# I2C_MUX.net
KiCad netlist of a schematic drawn in Altium Designer
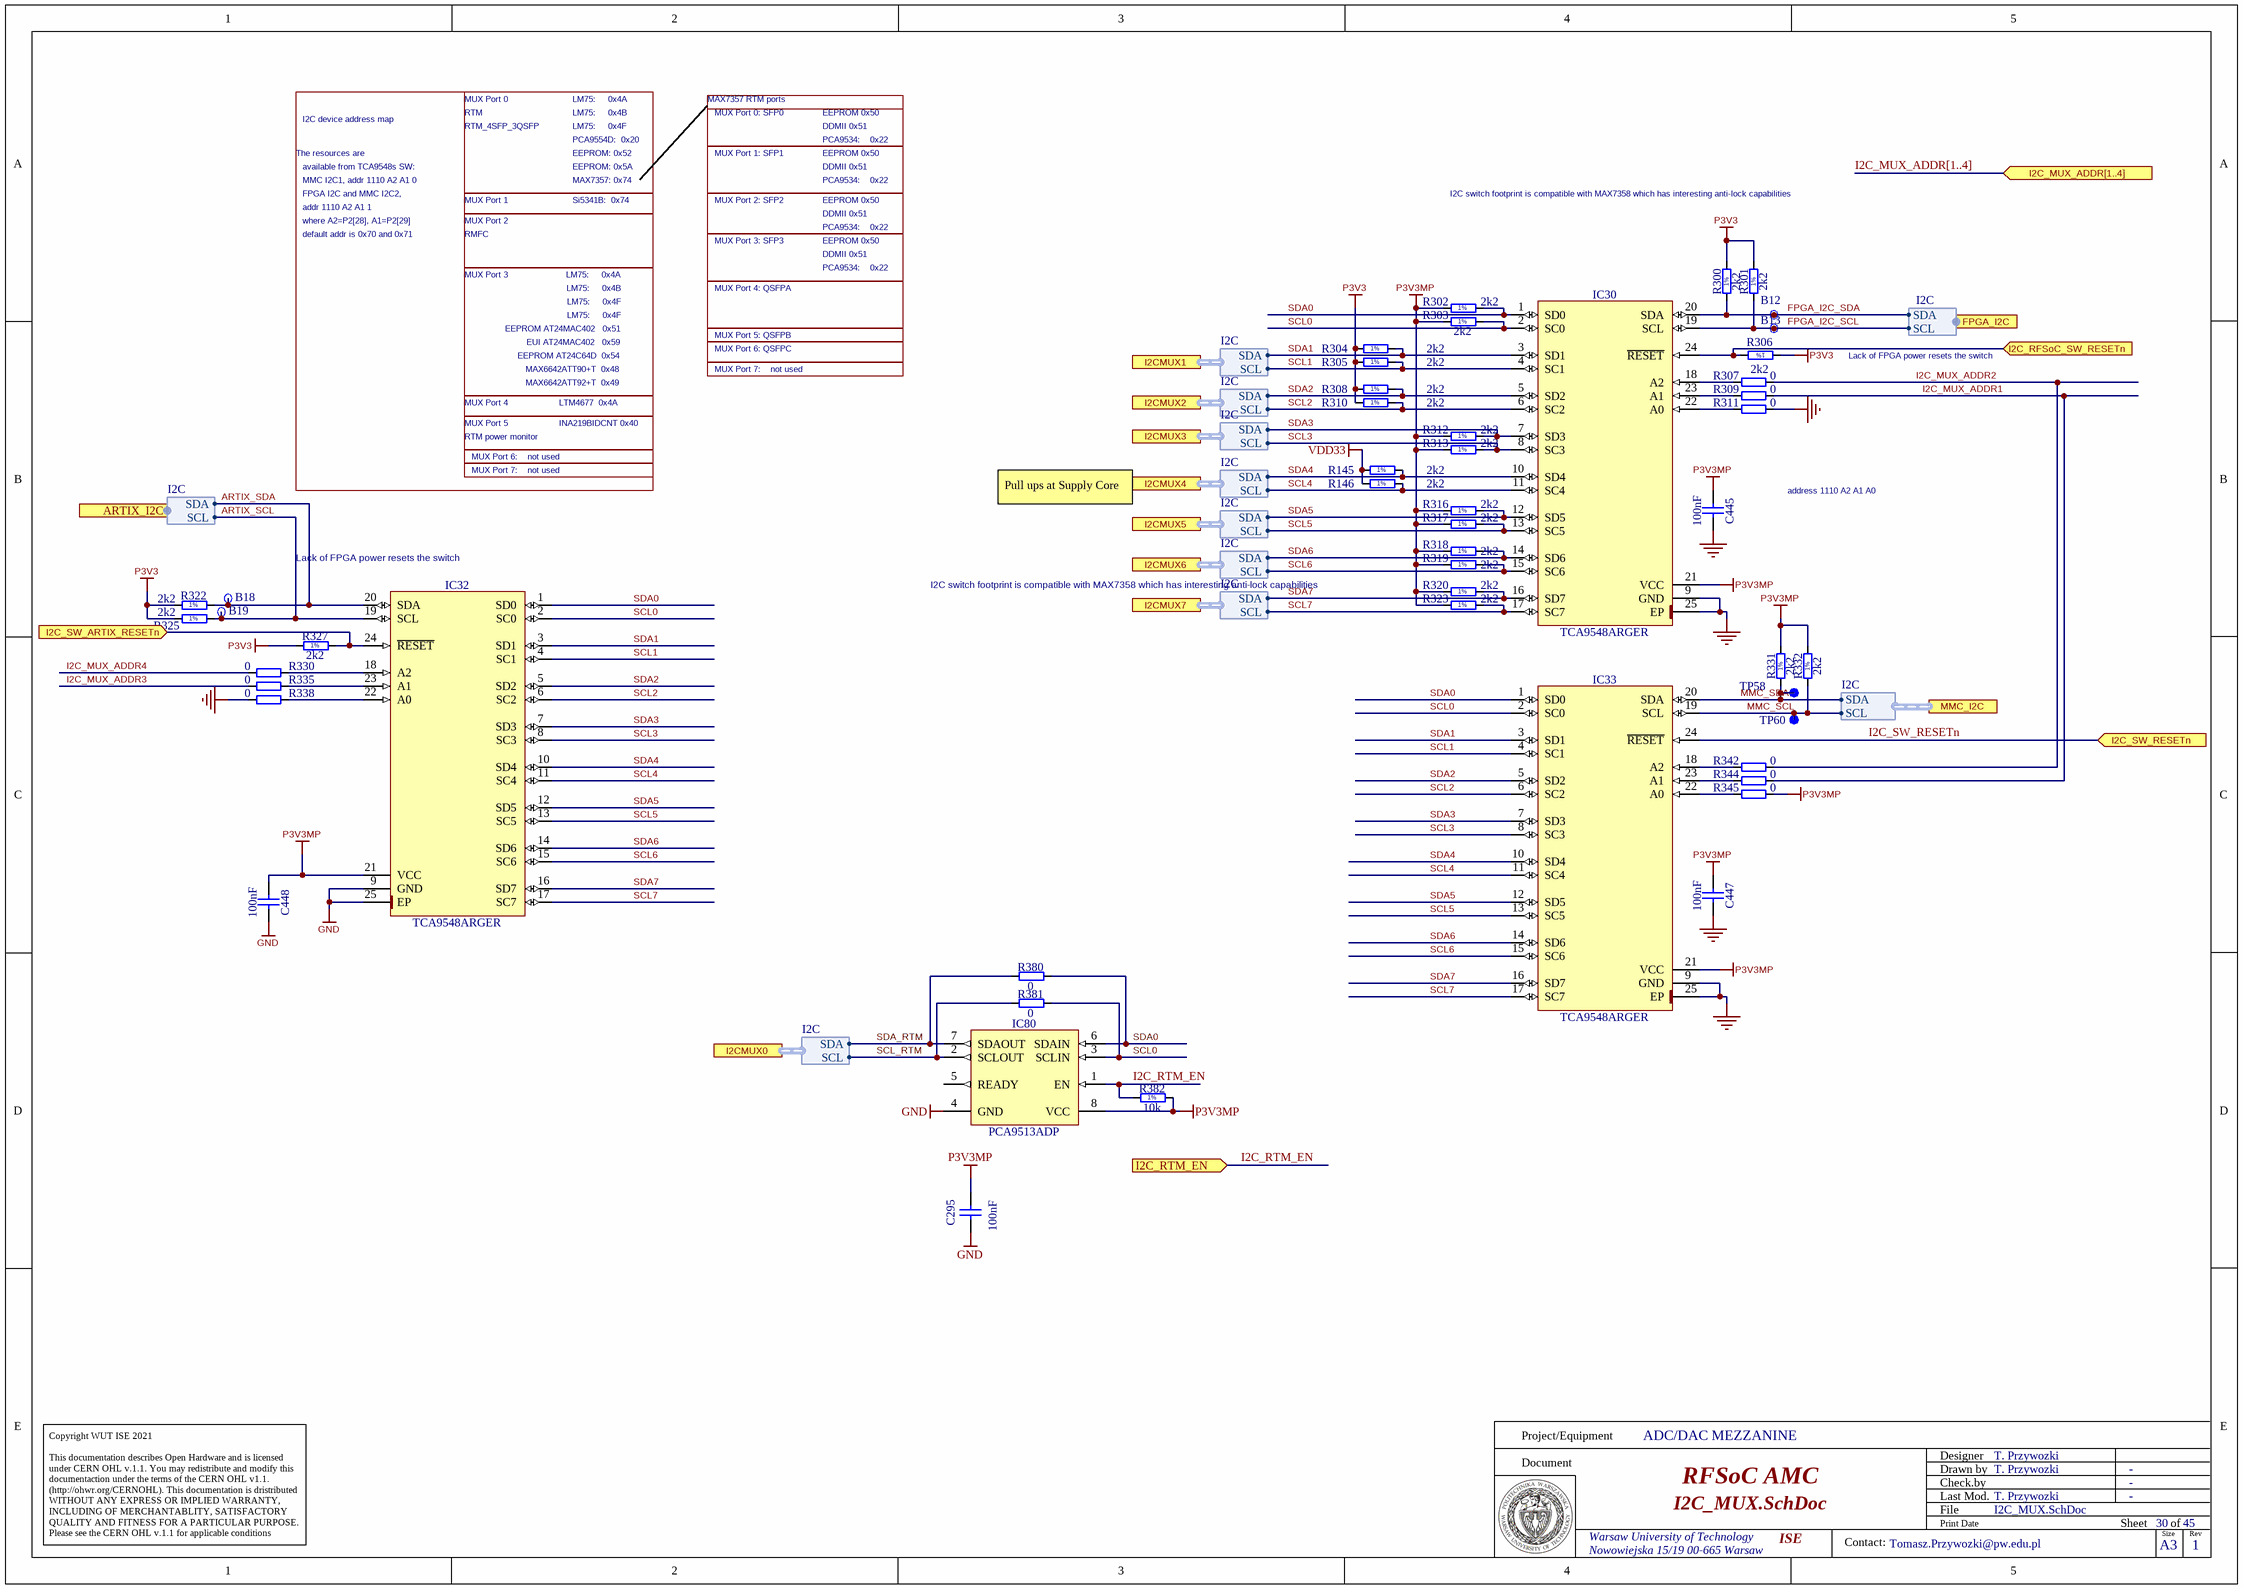
[diagram p0: I2C_MUX.SchDoc]

(export (version "E")
  (design (tool "Eeschema 10.0.6"))
  (components
    (comp (ref "B12")
      (value "SMD_PAD_D1MM")
      (footprint "C100")
      (libsource (lib "altium-import") (part "root_0__*"))
    )
    (comp (ref "B13")
      (value "SMD_PAD_D1MM")
      (footprint "C100")
      (libsource (lib "altium-import") (part "root_0__*"))
    )
    (comp (ref "B18")
      (value "SMD_PAD_D1MM")
      (footprint "C100")
      (libsource (lib "altium-import") (part "root_0__*"))
    )
    (comp (ref "B19")
      (value "SMD_PAD_D1MM")
      (footprint "C100")
      (libsource (lib "altium-import") (part "root_0__*"))
    )
    (comp (ref "C295")
      (value "100nF")
      (footprint "CAPC0603X33N")
      (description "Non-polarised capacitor")
      (fields
        (field (name "MANUFACTURER PART NUMBER") "CC0201_100NF_6.3V_10%_X5R")
        (field (name "MANUFACTURER") "GENERIC")
        (field (name "AUTHOR") "CERN DEM JLC")
      )
      (libsource (lib "Capacitors") (part "Capacitor - non polarized"))
    )
    (comp (ref "C445")
      (value "100nF")
      (footprint "CAPC0603X33N")
      (description "Non-polarised capacitor")
      (fields
        (field (name "MANUFACTURER PART NUMBER") "CC0201_100NF_6.3V_10%_X5R")
        (field (name "MANUFACTURER") "GENERIC")
        (field (name "AUTHOR") "CERN DEM JLC")
      )
      (libsource (lib "Capacitors") (part "Capacitor - non polarized"))
    )
    (comp (ref "C447")
      (value "100nF")
      (footprint "CAPC0603X33N")
      (description "Non-polarised capacitor")
      (fields
        (field (name "MANUFACTURER PART NUMBER") "CC0201_100NF_6.3V_10%_X5R")
        (field (name "MANUFACTURER") "GENERIC")
        (field (name "AUTHOR") "CERN DEM JLC")
      )
      (libsource (lib "Capacitors") (part "Capacitor - non polarized"))
    )
    (comp (ref "C448")
      (value "100nF")
      (footprint "CAPC0603X33N")
      (description "Non-polarised capacitor")
      (fields
        (field (name "MANUFACTURER PART NUMBER") "CC0201_100NF_6.3V_10%_X5R")
        (field (name "MANUFACTURER") "GENERIC")
        (field (name "AUTHOR") "CERN DEM JLC")
      )
      (libsource (lib "Capacitors") (part "Capacitor - non polarized"))
    )
    (comp (ref "IC30")
      (value "TCA9548ARGER")
      (footprint "QFN50P400X400X100-25N-S220")
      (description "Low Voltage 8-Channel I2C Switch With Reset")
      (fields (field (name "MANUFACTURER") "TEXAS INSTRUMENTS") (field (name "AUTHOR") "CERN DEM JLC"))
      (libsource (lib "") (part "TCA9548ARGER_1"))
    )
    (comp (ref "IC32")
      (value "TCA9548ARGER")
      (footprint "QFN50P400X400X100-25N-S220")
      (description "Low Voltage 8-Channel I2C Switch With Reset")
      (fields (field (name "MANUFACTURER") "TEXAS INSTRUMENTS") (field (name "AUTHOR") "CERN DEM JLC"))
      (libsource (lib "ICs And Semiconductors") (part "TCA9548ARGER"))
    )
    (comp (ref "IC33")
      (value "TCA9548ARGER")
      (footprint "QFN50P400X400X100-25N-S220")
      (description "Low Voltage 8-Channel I2C Switch With Reset")
      (fields (field (name "MANUFACTURER") "TEXAS INSTRUMENTS") (field (name "AUTHOR") "CERN DEM JLC"))
      (libsource (lib "") (part "TCA9548ARGER_1"))
    )
    (comp (ref "IC80")
      (value "PCA9513ADP")
      (footprint "SOP65P490X110-8N")
      (description "Hot Swappable I2C-Bus and SMBus Bus Buffer")
      (fields (field (name "MANUFACTURER") "NXP SEMICONDUCTORS") (field (name "AUTHOR") "CERN DEM MR"))
      (libsource (lib "ICs And Semiconductors") (part "PCA9513A"))
    )
    (comp (ref "R145")
      (value "2k2")
      (footprint "RESC1005X40N")
      (description "Resistor - 1%")
      (fields
        (field (name "MANUFACTURER PART NUMBER") "R0402_2K2_1%_0.0625W_100PPM")
        (field (name "MANUFACTURER") "GENERIC")
        (field (name "AUTHOR") "CERN DEM JLC")
      )
      (libsource (lib "Resistors") (part "Resistor - 1%"))
    )
    (comp (ref "R146")
      (value "2k2")
      (footprint "RESC1005X40N")
      (description "Resistor - 1%")
      (fields
        (field (name "MANUFACTURER PART NUMBER") "R0402_2K2_1%_0.0625W_100PPM")
        (field (name "MANUFACTURER") "GENERIC")
        (field (name "AUTHOR") "CERN DEM JLC")
      )
      (libsource (lib "Resistors") (part "Resistor - 1%"))
    )
    (comp (ref "R300")
      (value "2k2")
      (footprint "RESC1005X40N")
      (description "Resistor - 1%")
      (fields
        (field (name "MANUFACTURER PART NUMBER") "R0402_2K2_1%_0.0625W_100PPM")
        (field (name "MANUFACTURER") "GENERIC")
        (field (name "AUTHOR") "CERN DEM JLC")
      )
      (libsource (lib "Resistors") (part "Resistor - 1%"))
    )
    (comp (ref "R301")
      (value "2k2")
      (footprint "RESC1005X40N")
      (description "Resistor - 1%")
      (fields
        (field (name "MANUFACTURER PART NUMBER") "R0402_2K2_1%_0.0625W_100PPM")
        (field (name "MANUFACTURER") "GENERIC")
        (field (name "AUTHOR") "CERN DEM JLC")
      )
      (libsource (lib "Resistors") (part "Resistor - 1%"))
    )
    (comp (ref "R302")
      (value "2k2")
      (footprint "RESC1005X40N")
      (description "Resistor - 1%")
      (fields
        (field (name "MANUFACTURER PART NUMBER") "R0402_2K2_1%_0.0625W_100PPM")
        (field (name "MANUFACTURER") "GENERIC")
        (field (name "AUTHOR") "CERN DEM JLC")
      )
      (libsource (lib "Resistors") (part "Resistor - 1%"))
    )
    (comp (ref "R303")
      (value "2k2")
      (footprint "RESC1005X40N")
      (description "Resistor - 1%")
      (fields
        (field (name "MANUFACTURER PART NUMBER") "R0402_2K2_1%_0.0625W_100PPM")
        (field (name "MANUFACTURER") "GENERIC")
        (field (name "AUTHOR") "CERN DEM JLC")
      )
      (libsource (lib "Resistors") (part "Resistor - 1%"))
    )
    (comp (ref "R304")
      (value "2k2")
      (footprint "RESC1005X40N")
      (description "Resistor - 1%")
      (fields
        (field (name "MANUFACTURER PART NUMBER") "R0402_2K2_1%_0.0625W_100PPM")
        (field (name "MANUFACTURER") "GENERIC")
        (field (name "AUTHOR") "CERN DEM JLC")
      )
      (libsource (lib "Resistors") (part "Resistor - 1%"))
    )
    (comp (ref "R305")
      (value "2k2")
      (footprint "RESC1005X40N")
      (description "Resistor - 1%")
      (fields
        (field (name "MANUFACTURER PART NUMBER") "R0402_2K2_1%_0.0625W_100PPM")
        (field (name "MANUFACTURER") "GENERIC")
        (field (name "AUTHOR") "CERN DEM JLC")
      )
      (libsource (lib "Resistors") (part "Resistor - 1%"))
    )
    (comp (ref "R306")
      (value "2k2")
      (footprint "RESC1005X40N")
      (description "Resistor - 1%")
      (fields
        (field (name "MANUFACTURER PART NUMBER") "R0402_2K2_1%_0.0625W_100PPM")
        (field (name "MANUFACTURER") "GENERIC")
        (field (name "AUTHOR") "CERN DEM JLC")
      )
      (libsource (lib "Resistors") (part "Resistor - 1%"))
    )
    (comp (ref "R307")
      (value "0")
      (footprint "RESC1005X40N")
      (description "Resistor")
      (fields
        (field (name "MANUFACTURER PART NUMBER") "R0402_0R_JUMPER")
        (field (name "MANUFACTURER") "GENERIC")
        (field (name "AUTHOR") "CERN DEM JLC")
      )
      (libsource (lib "Resistors") (part "Resistor"))
    )
    (comp (ref "R308")
      (value "2k2")
      (footprint "RESC1005X40N")
      (description "Resistor - 1%")
      (fields
        (field (name "MANUFACTURER PART NUMBER") "R0402_2K2_1%_0.0625W_100PPM")
        (field (name "MANUFACTURER") "GENERIC")
        (field (name "AUTHOR") "CERN DEM JLC")
      )
      (libsource (lib "Resistors") (part "Resistor - 1%"))
    )
    (comp (ref "R309")
      (value "0")
      (footprint "RESC1005X40N")
      (description "Resistor")
      (fields
        (field (name "MANUFACTURER PART NUMBER") "R0402_0R_JUMPER")
        (field (name "MANUFACTURER") "GENERIC")
        (field (name "AUTHOR") "CERN DEM JLC")
      )
      (libsource (lib "Resistors") (part "Resistor"))
    )
    (comp (ref "R310")
      (value "2k2")
      (footprint "RESC1005X40N")
      (description "Resistor - 1%")
      (fields
        (field (name "MANUFACTURER PART NUMBER") "R0402_2K2_1%_0.0625W_100PPM")
        (field (name "MANUFACTURER") "GENERIC")
        (field (name "AUTHOR") "CERN DEM JLC")
      )
      (libsource (lib "Resistors") (part "Resistor - 1%"))
    )
    (comp (ref "R311")
      (value "0")
      (footprint "RESC1005X40N")
      (description "Resistor")
      (fields
        (field (name "MANUFACTURER PART NUMBER") "R0402_0R_JUMPER")
        (field (name "MANUFACTURER") "GENERIC")
        (field (name "AUTHOR") "CERN DEM JLC")
      )
      (libsource (lib "Resistors") (part "Resistor"))
    )
    (comp (ref "R312")
      (value "2k2")
      (footprint "RESC1005X40N")
      (description "Resistor - 1%")
      (fields
        (field (name "MANUFACTURER PART NUMBER") "R0402_2K2_1%_0.0625W_100PPM")
        (field (name "MANUFACTURER") "GENERIC")
        (field (name "AUTHOR") "CERN DEM JLC")
      )
      (libsource (lib "Resistors") (part "Resistor - 1%"))
    )
    (comp (ref "R313")
      (value "2k2")
      (footprint "RESC1005X40N")
      (description "Resistor - 1%")
      (fields
        (field (name "MANUFACTURER PART NUMBER") "R0402_2K2_1%_0.0625W_100PPM")
        (field (name "MANUFACTURER") "GENERIC")
        (field (name "AUTHOR") "CERN DEM JLC")
      )
      (libsource (lib "Resistors") (part "Resistor - 1%"))
    )
    (comp (ref "R316")
      (value "2k2")
      (footprint "RESC1005X40N")
      (description "Resistor - 1%")
      (fields
        (field (name "MANUFACTURER PART NUMBER") "R0402_2K2_1%_0.0625W_100PPM")
        (field (name "MANUFACTURER") "GENERIC")
        (field (name "AUTHOR") "CERN DEM JLC")
      )
      (libsource (lib "Resistors") (part "Resistor - 1%"))
    )
    (comp (ref "R317")
      (value "2k2")
      (footprint "RESC1005X40N")
      (description "Resistor - 1%")
      (fields
        (field (name "MANUFACTURER PART NUMBER") "R0402_2K2_1%_0.0625W_100PPM")
        (field (name "MANUFACTURER") "GENERIC")
        (field (name "AUTHOR") "CERN DEM JLC")
      )
      (libsource (lib "Resistors") (part "Resistor - 1%"))
    )
    (comp (ref "R318")
      (value "2k2")
      (footprint "RESC1005X40N")
      (description "Resistor - 1%")
      (fields
        (field (name "MANUFACTURER PART NUMBER") "R0402_2K2_1%_0.0625W_100PPM")
        (field (name "MANUFACTURER") "GENERIC")
        (field (name "AUTHOR") "CERN DEM JLC")
      )
      (libsource (lib "Resistors") (part "Resistor - 1%"))
    )
    (comp (ref "R319")
      (value "2k2")
      (footprint "RESC1005X40N")
      (description "Resistor - 1%")
      (fields
        (field (name "MANUFACTURER PART NUMBER") "R0402_2K2_1%_0.0625W_100PPM")
        (field (name "MANUFACTURER") "GENERIC")
        (field (name "AUTHOR") "CERN DEM JLC")
      )
      (libsource (lib "Resistors") (part "Resistor - 1%"))
    )
    (comp (ref "R320")
      (value "2k2")
      (footprint "RESC1005X40N")
      (description "Resistor - 1%")
      (fields
        (field (name "MANUFACTURER PART NUMBER") "R0402_2K2_1%_0.0625W_100PPM")
        (field (name "MANUFACTURER") "GENERIC")
        (field (name "AUTHOR") "CERN DEM JLC")
      )
      (libsource (lib "Resistors") (part "Resistor - 1%"))
    )
    (comp (ref "R322")
      (value "2k2")
      (footprint "RESC1005X40N")
      (description "Resistor - 1%")
      (fields
        (field (name "MANUFACTURER PART NUMBER") "R0402_2K2_1%_0.0625W_100PPM")
        (field (name "MANUFACTURER") "GENERIC")
        (field (name "AUTHOR") "CERN DEM JLC")
      )
      (libsource (lib "Resistors") (part "Resistor - 1%"))
    )
    (comp (ref "R323")
      (value "2k2")
      (footprint "RESC1005X40N")
      (description "Resistor - 1%")
      (fields
        (field (name "MANUFACTURER PART NUMBER") "R0402_2K2_1%_0.0625W_100PPM")
        (field (name "MANUFACTURER") "GENERIC")
        (field (name "AUTHOR") "CERN DEM JLC")
      )
      (libsource (lib "Resistors") (part "Resistor - 1%"))
    )
    (comp (ref "R325")
      (value "2k2")
      (footprint "RESC1005X40N")
      (description "Resistor - 1%")
      (fields
        (field (name "MANUFACTURER PART NUMBER") "R0402_2K2_1%_0.0625W_100PPM")
        (field (name "MANUFACTURER") "GENERIC")
        (field (name "AUTHOR") "CERN DEM JLC")
      )
      (libsource (lib "Resistors") (part "Resistor - 1%"))
    )
    (comp (ref "R327")
      (value "2k2")
      (footprint "RESC1005X40N")
      (description "Resistor - 1%")
      (fields
        (field (name "MANUFACTURER PART NUMBER") "R0402_2K2_1%_0.0625W_100PPM")
        (field (name "MANUFACTURER") "GENERIC")
        (field (name "AUTHOR") "CERN DEM JLC")
      )
      (libsource (lib "Resistors") (part "Resistor - 1%"))
    )
    (comp (ref "R330")
      (value "0")
      (footprint "RESC1005X40N")
      (description "Resistor")
      (fields
        (field (name "MANUFACTURER PART NUMBER") "R0402_0R_JUMPER")
        (field (name "MANUFACTURER") "GENERIC")
        (field (name "AUTHOR") "CERN DEM JLC")
      )
      (libsource (lib "Resistors") (part "Resistor"))
    )
    (comp (ref "R331")
      (value "2k2")
      (footprint "RESC1005X40N")
      (description "Resistor - 1%")
      (fields
        (field (name "MANUFACTURER PART NUMBER") "R0402_2K2_1%_0.0625W_100PPM")
        (field (name "MANUFACTURER") "GENERIC")
        (field (name "AUTHOR") "CERN DEM JLC")
      )
      (libsource (lib "Resistors") (part "Resistor - 1%"))
    )
    (comp (ref "R332")
      (value "2k2")
      (footprint "RESC1005X40N")
      (description "Resistor - 1%")
      (fields
        (field (name "MANUFACTURER PART NUMBER") "R0402_2K2_1%_0.0625W_100PPM")
        (field (name "MANUFACTURER") "GENERIC")
        (field (name "AUTHOR") "CERN DEM JLC")
      )
      (libsource (lib "Resistors") (part "Resistor - 1%"))
    )
    (comp (ref "R335")
      (value "0")
      (footprint "RESC1005X40N")
      (description "Resistor")
      (fields
        (field (name "MANUFACTURER PART NUMBER") "R0402_0R_JUMPER")
        (field (name "MANUFACTURER") "GENERIC")
        (field (name "AUTHOR") "CERN DEM JLC")
      )
      (libsource (lib "Resistors") (part "Resistor"))
    )
    (comp (ref "R338")
      (value "0")
      (footprint "RESC1005X40N")
      (description "Resistor")
      (fields
        (field (name "MANUFACTURER PART NUMBER") "R0402_0R_JUMPER")
        (field (name "MANUFACTURER") "GENERIC")
        (field (name "AUTHOR") "CERN DEM JLC")
      )
      (libsource (lib "Resistors") (part "Resistor"))
    )
    (comp (ref "R342")
      (value "0")
      (footprint "RESC1005X40N")
      (description "Resistor")
      (fields
        (field (name "MANUFACTURER PART NUMBER") "R0402_0R_JUMPER")
        (field (name "MANUFACTURER") "GENERIC")
        (field (name "AUTHOR") "CERN DEM JLC")
      )
      (libsource (lib "Resistors") (part "Resistor"))
    )
    (comp (ref "R344")
      (value "0")
      (footprint "RESC1005X40N")
      (description "Resistor")
      (fields
        (field (name "MANUFACTURER PART NUMBER") "R0402_0R_JUMPER")
        (field (name "MANUFACTURER") "GENERIC")
        (field (name "AUTHOR") "CERN DEM JLC")
      )
      (libsource (lib "Resistors") (part "Resistor"))
    )
    (comp (ref "R345")
      (value "0")
      (footprint "RESC1005X40N")
      (description "Resistor")
      (fields
        (field (name "MANUFACTURER PART NUMBER") "R0402_0R_JUMPER")
        (field (name "MANUFACTURER") "GENERIC")
        (field (name "AUTHOR") "CERN DEM JLC")
      )
      (libsource (lib "Resistors") (part "Resistor"))
    )
    (comp (ref "R380")
      (value "0")
      (footprint "RESC1005X40N")
      (description "Resistor")
      (fields
        (field (name "PART NUMBER") "R0402_0R_JUMPER")
        (field (name "MANUFACTURER") "GENERIC")
        (field (name "AUTHOR") "CERN DEM JLC")
      )
      (libsource (lib "Resistors") (part "Resistor"))
    )
    (comp (ref "R381")
      (value "0")
      (footprint "RESC1005X40N")
      (description "Resistor")
      (fields
        (field (name "PART NUMBER") "R0402_0R_JUMPER")
        (field (name "MANUFACTURER") "GENERIC")
        (field (name "AUTHOR") "CERN DEM JLC")
      )
      (libsource (lib "Resistors") (part "Resistor"))
    )
    (comp (ref "R382")
      (value "10k")
      (footprint "RESC1005X40N")
      (description "Resistor - 1%")
      (fields
        (field (name "PART NUMBER") "R0402_10K_1%_0.0625W_100PPM")
        (field (name "POWER") "0.0625W")
        (field (name "AUTHOR") "CERN DEM JLC")
      )
      (libsource (lib "Resistors") (part "Resistor - 1%"))
    )
    (comp (ref "TP58")
      (value "SMD Pad")
      (footprint "C100")
      (description "Through Hole Pad")
      (fields (field (name "PART NUMBER") "SMD_PAD_D1MM") (field (name "AUTHOR") "CERN DEM JLC"))
      (libsource (lib "Eletro-mechanical") (part "Single SMD Pad (Round)"))
    )
    (comp (ref "TP60")
      (value "SMD Pad")
      (footprint "C100")
      (description "Through Hole Pad")
      (fields (field (name "PART NUMBER") "SMD_PAD_D1MM") (field (name "AUTHOR") "CERN DEM JLC"))
      (libsource (lib "Eletro-mechanical") (part "Single SMD Pad (Round)"))
    )
  )
  (nets
    (net (code "2") (name "/ARTIX_SCL") (class "Default")
      (node (ref "B19") (pin "1") (pinfunction "1_1") (pintype "passive"))
      (node (ref "IC32") (pin "19") (pinfunction "SCL_19") (pintype "bidirectional"))
      (node (ref "R325") (pin "1") (pinfunction "1_1") (pintype "passive"))
    )
    (net (code "3") (name "/ARTIX_SDA") (class "Default")
      (node (ref "B18") (pin "1") (pinfunction "1_1") (pintype "passive"))
      (node (ref "IC32") (pin "20") (pinfunction "SDA_20") (pintype "bidirectional"))
      (node (ref "R322") (pin "1") (pinfunction "1_1") (pintype "passive"))
    )
    (net (code "4") (name "/FPGA_I2C_SCL") (class "Default")
      (node (ref "B13") (pin "1") (pinfunction "1_1") (pintype "passive"))
      (node (ref "IC30") (pin "19") (pinfunction "SCL_19") (pintype "bidirectional"))
      (node (ref "R301") (pin "1") (pinfunction "1_1") (pintype "passive"))
    )
    (net (code "5") (name "/FPGA_I2C_SDA") (class "Default")
      (node (ref "B12") (pin "1") (pinfunction "1_1") (pintype "passive"))
      (node (ref "IC30") (pin "20") (pinfunction "SDA_20") (pintype "bidirectional"))
      (node (ref "R300") (pin "1") (pinfunction "1_1") (pintype "passive"))
    )
    (net (code "6") (name "/I2C_MUX_ADDR1") (class "Default")
      (node (ref "R309") (pin "1") (pinfunction "1_1") (pintype "passive"))
      (node (ref "R344") (pin "1") (pinfunction "1_1") (pintype "passive"))
    )
    (net (code "7") (name "/I2C_MUX_ADDR2") (class "Default")
      (node (ref "R307") (pin "1") (pinfunction "1_1") (pintype "passive"))
      (node (ref "R342") (pin "1") (pinfunction "1_1") (pintype "passive"))
    )
    (net (code "8") (name "/I2C_MUX_ADDR3") (class "Default")
      (node (ref "R335") (pin "2") (pinfunction "2_2") (pintype "passive"))
    )
    (net (code "9") (name "/I2C_MUX_ADDR4") (class "Default")
      (node (ref "R330") (pin "2") (pinfunction "2_2") (pintype "passive"))
    )
    (net (code "11") (name "/I2C_RFSoC_SW_RESETn") (class "Default")
      (node (ref "IC30") (pin "24") (pinfunction "~{RESET}_24") (pintype "input"))
      (node (ref "R306") (pin "2") (pinfunction "2_2") (pintype "passive"))
    )
    (net (code "12") (name "/I2C_RTM_EN") (class "Default")
      (node (ref "IC80") (pin "1") (pinfunction "EN_1") (pintype "input"))
      (node (ref "R382") (pin "1") (pinfunction "1_1") (pintype "passive"))
    )
    (net (code "13") (name "/I2C_SW_ARTIX_RESETn") (class "Default")
      (node (ref "IC32") (pin "24") (pinfunction "~{RESET}_24") (pintype "input"))
      (node (ref "R327") (pin "1") (pinfunction "1_1") (pintype "passive"))
    )
    (net (code "14") (name "/I2C_SW_RESETn") (class "Default")
      (node (ref "IC33") (pin "24") (pinfunction "~{RESET}_24") (pintype "input"))
    )
    (net (code "15") (name "/MMC_SCL") (class "Default")
      (node (ref "IC33") (pin "19") (pinfunction "SCL_19") (pintype "bidirectional"))
      (node (ref "R332") (pin "1") (pinfunction "1_1") (pintype "passive"))
      (node (ref "TP60") (pin "1") (pinfunction "1_1") (pintype "bidirectional"))
    )
    (net (code "16") (name "/MMC_SDA") (class "Default")
      (node (ref "IC33") (pin "20") (pinfunction "SDA_20") (pintype "bidirectional"))
      (node (ref "R331") (pin "1") (pinfunction "1_1") (pintype "passive"))
      (node (ref "TP58") (pin "1") (pinfunction "1_1") (pintype "bidirectional"))
    )
    (net (code "17") (name "/SCL0") (class "Default")
      (node (ref "IC30") (pin "2") (pinfunction "SC0_2") (pintype "bidirectional"))
      (node (ref "IC32") (pin "2") (pinfunction "SC0_2") (pintype "bidirectional"))
      (node (ref "IC33") (pin "2") (pinfunction "SC0_2") (pintype "bidirectional"))
      (node (ref "IC80") (pin "3") (pinfunction "SCLIN_3") (pintype "input"))
      (node (ref "R303") (pin "2") (pinfunction "2_2") (pintype "passive"))
      (node (ref "R381") (pin "2") (pinfunction "2_2") (pintype "passive"))
    )
    (net (code "18") (name "/SCL1") (class "Default")
      (node (ref "IC30") (pin "4") (pinfunction "SC1_4") (pintype "bidirectional"))
      (node (ref "IC32") (pin "4") (pinfunction "SC1_4") (pintype "bidirectional"))
      (node (ref "IC33") (pin "4") (pinfunction "SC1_4") (pintype "bidirectional"))
      (node (ref "R305") (pin "2") (pinfunction "2_2") (pintype "passive"))
    )
    (net (code "19") (name "/SCL2") (class "Default")
      (node (ref "IC30") (pin "6") (pinfunction "SC2_6") (pintype "bidirectional"))
      (node (ref "IC32") (pin "6") (pinfunction "SC2_6") (pintype "bidirectional"))
      (node (ref "IC33") (pin "6") (pinfunction "SC2_6") (pintype "bidirectional"))
      (node (ref "R310") (pin "2") (pinfunction "2_2") (pintype "passive"))
    )
    (net (code "20") (name "/SCL3") (class "Default")
      (node (ref "IC30") (pin "8") (pinfunction "SC3_8") (pintype "bidirectional"))
      (node (ref "IC32") (pin "8") (pinfunction "SC3_8") (pintype "bidirectional"))
      (node (ref "IC33") (pin "8") (pinfunction "SC3_8") (pintype "bidirectional"))
      (node (ref "R313") (pin "2") (pinfunction "2_2") (pintype "passive"))
    )
    (net (code "21") (name "/SCL4") (class "Default")
      (node (ref "IC30") (pin "11") (pinfunction "SC4_11") (pintype "bidirectional"))
      (node (ref "IC32") (pin "11") (pinfunction "SC4_11") (pintype "bidirectional"))
      (node (ref "IC33") (pin "11") (pinfunction "SC4_11") (pintype "bidirectional"))
      (node (ref "R146") (pin "2") (pinfunction "2_2") (pintype "passive"))
    )
    (net (code "22") (name "/SCL5") (class "Default")
      (node (ref "IC30") (pin "13") (pinfunction "SC5_13") (pintype "bidirectional"))
      (node (ref "IC32") (pin "13") (pinfunction "SC5_13") (pintype "bidirectional"))
      (node (ref "IC33") (pin "13") (pinfunction "SC5_13") (pintype "bidirectional"))
      (node (ref "R317") (pin "2") (pinfunction "2_2") (pintype "passive"))
    )
    (net (code "23") (name "/SCL6") (class "Default")
      (node (ref "IC30") (pin "15") (pinfunction "SC6_15") (pintype "bidirectional"))
      (node (ref "IC32") (pin "15") (pinfunction "SC6_15") (pintype "bidirectional"))
      (node (ref "IC33") (pin "15") (pinfunction "SC6_15") (pintype "bidirectional"))
      (node (ref "R319") (pin "2") (pinfunction "2_2") (pintype "passive"))
    )
    (net (code "24") (name "/SCL7") (class "Default")
      (node (ref "IC30") (pin "17") (pinfunction "SC7_17") (pintype "bidirectional"))
      (node (ref "IC32") (pin "17") (pinfunction "SC7_17") (pintype "bidirectional"))
      (node (ref "IC33") (pin "17") (pinfunction "SC7_17") (pintype "bidirectional"))
      (node (ref "R323") (pin "2") (pinfunction "2_2") (pintype "passive"))
    )
    (net (code "25") (name "/SCL_RTM") (class "Default")
      (node (ref "IC80") (pin "2") (pinfunction "SCLOUT_2") (pintype "output"))
      (node (ref "R381") (pin "1") (pinfunction "1_1") (pintype "passive"))
    )
    (net (code "26") (name "/SDA0") (class "Default")
      (node (ref "IC30") (pin "1") (pinfunction "SD0_1") (pintype "bidirectional"))
      (node (ref "IC32") (pin "1") (pinfunction "SD0_1") (pintype "bidirectional"))
      (node (ref "IC33") (pin "1") (pinfunction "SD0_1") (pintype "bidirectional"))
      (node (ref "IC80") (pin "6") (pinfunction "SDAIN_6") (pintype "input"))
      (node (ref "R302") (pin "2") (pinfunction "2_2") (pintype "passive"))
      (node (ref "R380") (pin "2") (pinfunction "2_2") (pintype "passive"))
    )
    (net (code "27") (name "/SDA1") (class "Default")
      (node (ref "IC30") (pin "3") (pinfunction "SD1_3") (pintype "bidirectional"))
      (node (ref "IC32") (pin "3") (pinfunction "SD1_3") (pintype "bidirectional"))
      (node (ref "IC33") (pin "3") (pinfunction "SD1_3") (pintype "bidirectional"))
      (node (ref "R304") (pin "2") (pinfunction "2_2") (pintype "passive"))
    )
    (net (code "28") (name "/SDA2") (class "Default")
      (node (ref "IC30") (pin "5") (pinfunction "SD2_5") (pintype "bidirectional"))
      (node (ref "IC32") (pin "5") (pinfunction "SD2_5") (pintype "bidirectional"))
      (node (ref "IC33") (pin "5") (pinfunction "SD2_5") (pintype "bidirectional"))
      (node (ref "R308") (pin "2") (pinfunction "2_2") (pintype "passive"))
    )
    (net (code "29") (name "/SDA3") (class "Default")
      (node (ref "IC30") (pin "7") (pinfunction "SD3_7") (pintype "bidirectional"))
      (node (ref "IC32") (pin "7") (pinfunction "SD3_7") (pintype "bidirectional"))
      (node (ref "IC33") (pin "7") (pinfunction "SD3_7") (pintype "bidirectional"))
      (node (ref "R312") (pin "2") (pinfunction "2_2") (pintype "passive"))
    )
    (net (code "30") (name "/SDA4") (class "Default")
      (node (ref "IC30") (pin "10") (pinfunction "SD4_10") (pintype "bidirectional"))
      (node (ref "IC32") (pin "10") (pinfunction "SD4_10") (pintype "bidirectional"))
      (node (ref "IC33") (pin "10") (pinfunction "SD4_10") (pintype "bidirectional"))
      (node (ref "R145") (pin "2") (pinfunction "2_2") (pintype "passive"))
    )
    (net (code "31") (name "/SDA5") (class "Default")
      (node (ref "IC30") (pin "12") (pinfunction "SD5_12") (pintype "bidirectional"))
      (node (ref "IC32") (pin "12") (pinfunction "SD5_12") (pintype "bidirectional"))
      (node (ref "IC33") (pin "12") (pinfunction "SD5_12") (pintype "bidirectional"))
      (node (ref "R316") (pin "2") (pinfunction "2_2") (pintype "passive"))
    )
    (net (code "32") (name "/SDA6") (class "Default")
      (node (ref "IC30") (pin "14") (pinfunction "SD6_14") (pintype "bidirectional"))
      (node (ref "IC32") (pin "14") (pinfunction "SD6_14") (pintype "bidirectional"))
      (node (ref "IC33") (pin "14") (pinfunction "SD6_14") (pintype "bidirectional"))
      (node (ref "R318") (pin "2") (pinfunction "2_2") (pintype "passive"))
    )
    (net (code "33") (name "/SDA7") (class "Default")
      (node (ref "IC30") (pin "16") (pinfunction "SD7_16") (pintype "bidirectional"))
      (node (ref "IC32") (pin "16") (pinfunction "SD7_16") (pintype "bidirectional"))
      (node (ref "IC33") (pin "16") (pinfunction "SD7_16") (pintype "bidirectional"))
      (node (ref "R320") (pin "2") (pinfunction "2_2") (pintype "passive"))
    )
    (net (code "34") (name "/SDA_RTM") (class "Default")
      (node (ref "IC80") (pin "7") (pinfunction "SDAOUT_7") (pintype "output"))
      (node (ref "R380") (pin "1") (pinfunction "1_1") (pintype "passive"))
    )
    (net (code "36") (name "GND") (class "Default")
      (node (ref "C295") (pin "2") (pinfunction "2_2") (pintype "passive"))
      (node (ref "C445") (pin "2") (pinfunction "2_2") (pintype "passive"))
      (node (ref "C447") (pin "2") (pinfunction "2_2") (pintype "passive"))
      (node (ref "C448") (pin "1") (pinfunction "1_1") (pintype "passive"))
      (node (ref "IC30") (pin "25") (pinfunction "EP_25") (pintype "power_in"))
      (node (ref "IC30") (pin "9") (pinfunction "GND_9") (pintype "power_in"))
      (node (ref "IC32") (pin "25") (pinfunction "EP_25") (pintype "power_in"))
      (node (ref "IC32") (pin "9") (pinfunction "GND_9") (pintype "power_in"))
      (node (ref "IC33") (pin "25") (pinfunction "EP_25") (pintype "power_in"))
      (node (ref "IC33") (pin "9") (pinfunction "GND_9") (pintype "power_in"))
      (node (ref "IC80") (pin "4") (pinfunction "GND_4") (pintype "power_in"))
      (node (ref "R311") (pin "1") (pinfunction "1_1") (pintype "passive"))
      (node (ref "R338") (pin "2") (pinfunction "2_2") (pintype "passive"))
    )
    (net (code "37") (name "Net-(IC30-A0)") (class "Default")
      (node (ref "IC30") (pin "22") (pinfunction "A0_22") (pintype "input"))
      (node (ref "R311") (pin "2") (pinfunction "2_2") (pintype "passive"))
    )
    (net (code "38") (name "Net-(IC30-A1)") (class "Default")
      (node (ref "IC30") (pin "23") (pinfunction "A1_23") (pintype "input"))
      (node (ref "R309") (pin "2") (pinfunction "2_2") (pintype "passive"))
    )
    (net (code "39") (name "Net-(IC30-A2)") (class "Default")
      (node (ref "IC30") (pin "18") (pinfunction "A2_18") (pintype "input"))
      (node (ref "R307") (pin "2") (pinfunction "2_2") (pintype "passive"))
    )
    (net (code "40") (name "Net-(IC32-A0)") (class "Default")
      (node (ref "IC32") (pin "22") (pinfunction "A0_22") (pintype "input"))
      (node (ref "R338") (pin "1") (pinfunction "1_1") (pintype "passive"))
    )
    (net (code "41") (name "Net-(IC32-A1)") (class "Default")
      (node (ref "IC32") (pin "23") (pinfunction "A1_23") (pintype "input"))
      (node (ref "R335") (pin "1") (pinfunction "1_1") (pintype "passive"))
    )
    (net (code "42") (name "Net-(IC32-A2)") (class "Default")
      (node (ref "IC32") (pin "18") (pinfunction "A2_18") (pintype "input"))
      (node (ref "R330") (pin "1") (pinfunction "1_1") (pintype "passive"))
    )
    (net (code "43") (name "Net-(IC33-A0)") (class "Default")
      (node (ref "IC33") (pin "22") (pinfunction "A0_22") (pintype "input"))
      (node (ref "R345") (pin "2") (pinfunction "2_2") (pintype "passive"))
    )
    (net (code "44") (name "Net-(IC33-A1)") (class "Default")
      (node (ref "IC33") (pin "23") (pinfunction "A1_23") (pintype "input"))
      (node (ref "R344") (pin "2") (pinfunction "2_2") (pintype "passive"))
    )
    (net (code "45") (name "Net-(IC33-A2)") (class "Default")
      (node (ref "IC33") (pin "18") (pinfunction "A2_18") (pintype "input"))
      (node (ref "R342") (pin "2") (pinfunction "2_2") (pintype "passive"))
    )
    (net (code "46") (name "P3V3") (class "Default")
      (node (ref "R300") (pin "2") (pinfunction "2_2") (pintype "passive"))
      (node (ref "R301") (pin "2") (pinfunction "2_2") (pintype "passive"))
      (node (ref "R304") (pin "1") (pinfunction "1_1") (pintype "passive"))
      (node (ref "R305") (pin "1") (pinfunction "1_1") (pintype "passive"))
      (node (ref "R306") (pin "1") (pinfunction "1_1") (pintype "passive"))
      (node (ref "R308") (pin "1") (pinfunction "1_1") (pintype "passive"))
      (node (ref "R310") (pin "1") (pinfunction "1_1") (pintype "passive"))
      (node (ref "R322") (pin "2") (pinfunction "2_2") (pintype "passive"))
      (node (ref "R325") (pin "2") (pinfunction "2_2") (pintype "passive"))
      (node (ref "R327") (pin "2") (pinfunction "2_2") (pintype "passive"))
    )
    (net (code "47") (name "P3V3MP") (class "Default")
      (node (ref "C295") (pin "1") (pinfunction "1_1") (pintype "passive"))
      (node (ref "C445") (pin "1") (pinfunction "1_1") (pintype "passive"))
      (node (ref "C447") (pin "1") (pinfunction "1_1") (pintype "passive"))
      (node (ref "C448") (pin "2") (pinfunction "2_2") (pintype "passive"))
      (node (ref "IC30") (pin "21") (pinfunction "VCC_21") (pintype "power_in"))
      (node (ref "IC32") (pin "21") (pinfunction "VCC_21") (pintype "power_in"))
      (node (ref "IC33") (pin "21") (pinfunction "VCC_21") (pintype "power_in"))
      (node (ref "IC80") (pin "8") (pinfunction "VCC_8") (pintype "power_in"))
      (node (ref "R302") (pin "1") (pinfunction "1_1") (pintype "passive"))
      (node (ref "R303") (pin "1") (pinfunction "1_1") (pintype "passive"))
      (node (ref "R312") (pin "1") (pinfunction "1_1") (pintype "passive"))
      (node (ref "R313") (pin "1") (pinfunction "1_1") (pintype "passive"))
      (node (ref "R316") (pin "1") (pinfunction "1_1") (pintype "passive"))
      (node (ref "R317") (pin "1") (pinfunction "1_1") (pintype "passive"))
      (node (ref "R318") (pin "1") (pinfunction "1_1") (pintype "passive"))
      (node (ref "R319") (pin "1") (pinfunction "1_1") (pintype "passive"))
      (node (ref "R320") (pin "1") (pinfunction "1_1") (pintype "passive"))
      (node (ref "R323") (pin "1") (pinfunction "1_1") (pintype "passive"))
      (node (ref "R331") (pin "2") (pinfunction "2_2") (pintype "passive"))
      (node (ref "R332") (pin "2") (pinfunction "2_2") (pintype "passive"))
      (node (ref "R345") (pin "1") (pinfunction "1_1") (pintype "passive"))
      (node (ref "R382") (pin "2") (pinfunction "2_2") (pintype "passive"))
    )
    (net (code "48") (name "VDD33") (class "Default")
      (node (ref "R145") (pin "1") (pinfunction "1_1") (pintype "passive"))
      (node (ref "R146") (pin "1") (pinfunction "1_1") (pintype "passive"))
    )
    (net (code "49") (name "unconnected-(IC80-READY-Pad5)") (class "Default")
      (node (ref "IC80") (pin "5") (pinfunction "READY_5") (pintype "output"))
    )
  )
)
